# AMU-S18-V00-CURRENTCurrentInterface.net
KiCad netlist of a schematic drawn in Altium Designer
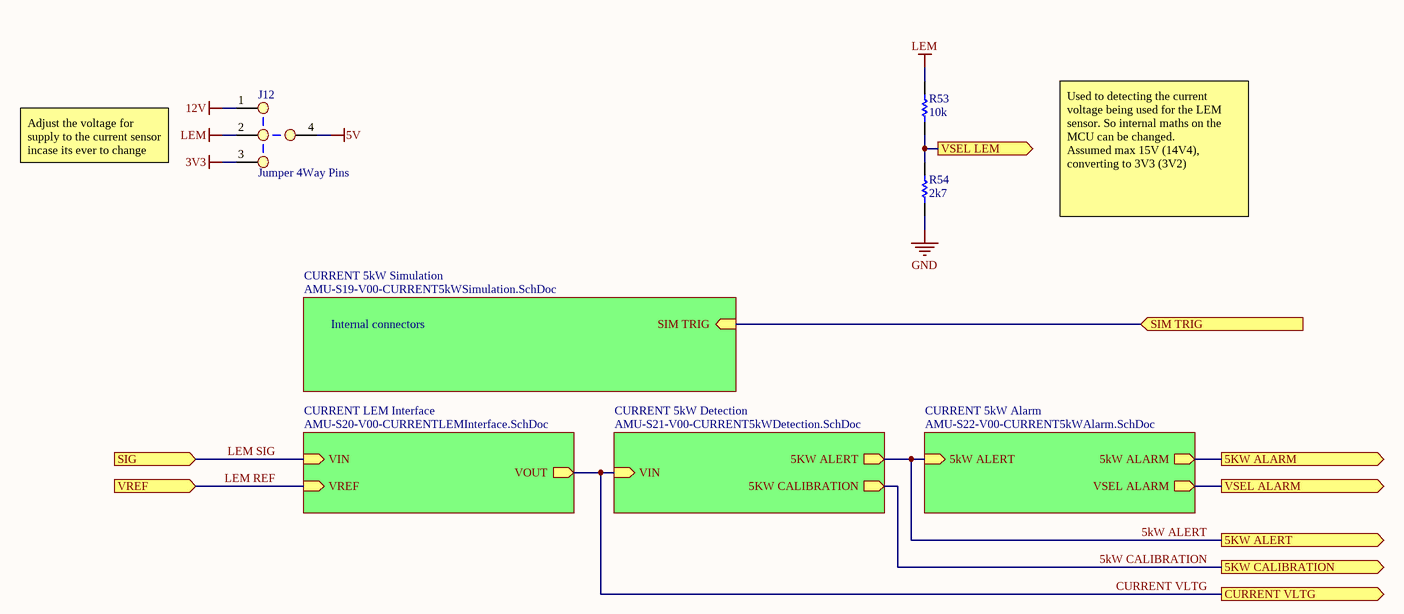
[diagram p0: AMU-S18-V00-CURRENTCurrentInterface.SchDoc]

(export (version "E")
  (design (tool "Eeschema 10.0.6"))
  (components
    (comp (ref "J12")
      (value "Jumper 4Way Pins")
      (footprint "Jumper_4Way_Pin")
      (libsource (lib "QUTMS_JumperLibrary") (part "Jumper 4Way Pins"))
    )
    (comp (ref "R53")
      (value "10k")
      (footprint "Res_ThinFilm_0603")
      (description "Resistor, SMD, 10k, 0.1W, 5%, 0603")
      (libsource (lib "StandardResistors") (part "10k 5% 0603"))
    )
    (comp (ref "R54")
      (value "2k7")
      (footprint "Res_ThinFilm_0603")
      (description "Resistor, SMD, 2k7, 0.1W, 5%, 0603")
      (libsource (lib "StandardResistors") (part "2k7 5% 0603"))
    )
  )
  (nets
    (net (code "9") (name "/VSEL LEM") (class "Default")
      (node (ref "R53") (pin "1") (pinfunction "1_1") (pintype "passive"))
      (node (ref "R54") (pin "2") (pinfunction "2_2") (pintype "passive"))
    )
    (net (code "10") (name "3V3") (class "Default")
      (node (ref "J12") (pin "3") (pinfunction "3_3") (pintype "passive"))
    )
    (net (code "11") (name "5V") (class "Default")
      (node (ref "J12") (pin "4") (pinfunction "4_4") (pintype "passive"))
    )
    (net (code "12") (name "12V") (class "Default")
      (node (ref "J12") (pin "1") (pinfunction "1_1") (pintype "passive"))
    )
    (net (code "13") (name "GND") (class "Default")
      (node (ref "R54") (pin "1") (pinfunction "1_1") (pintype "passive"))
    )
    (net (code "14") (name "LEM") (class "Default")
      (node (ref "J12") (pin "2") (pinfunction "2_2") (pintype "passive"))
      (node (ref "R53") (pin "2") (pinfunction "2_2") (pintype "passive"))
    )
  )
)
